# digital_gpio.net
KiCad netlist of a schematic drawn in Altium Designer
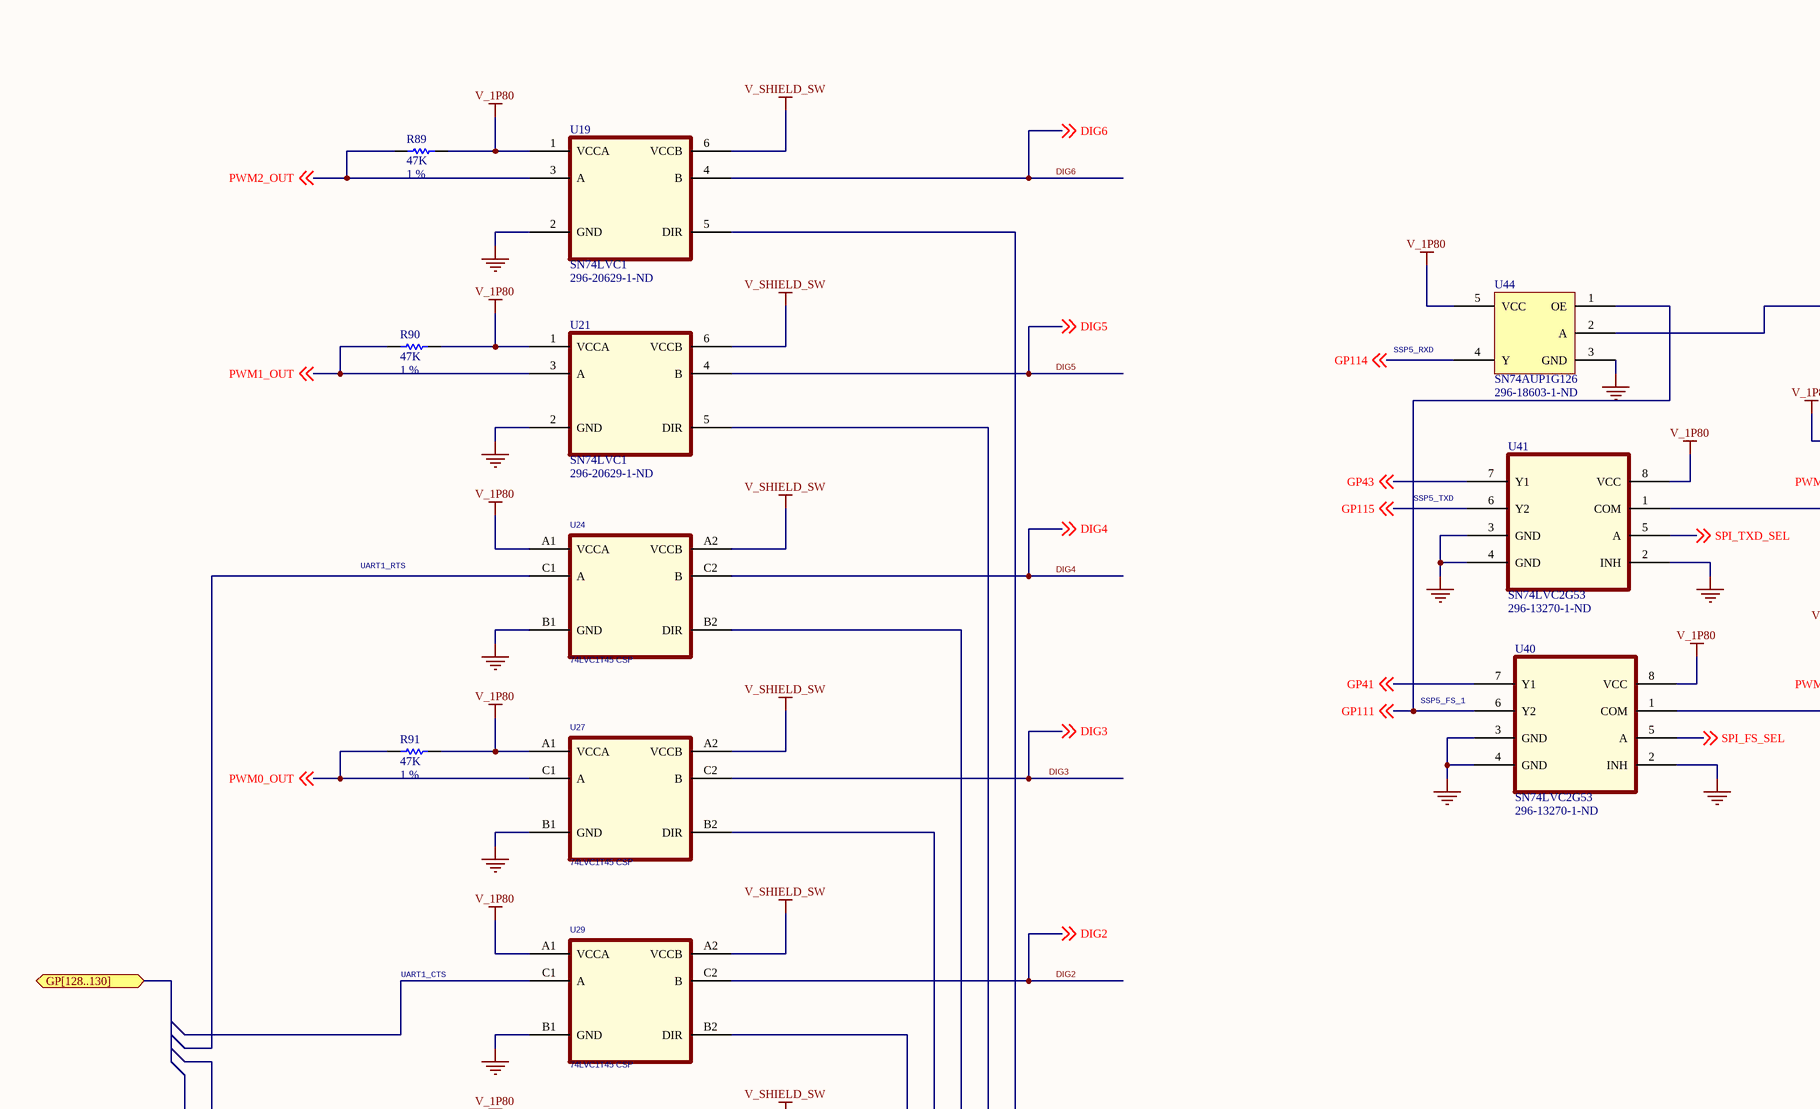
[diagram p0: digital_gpio.SchDoc, top left]
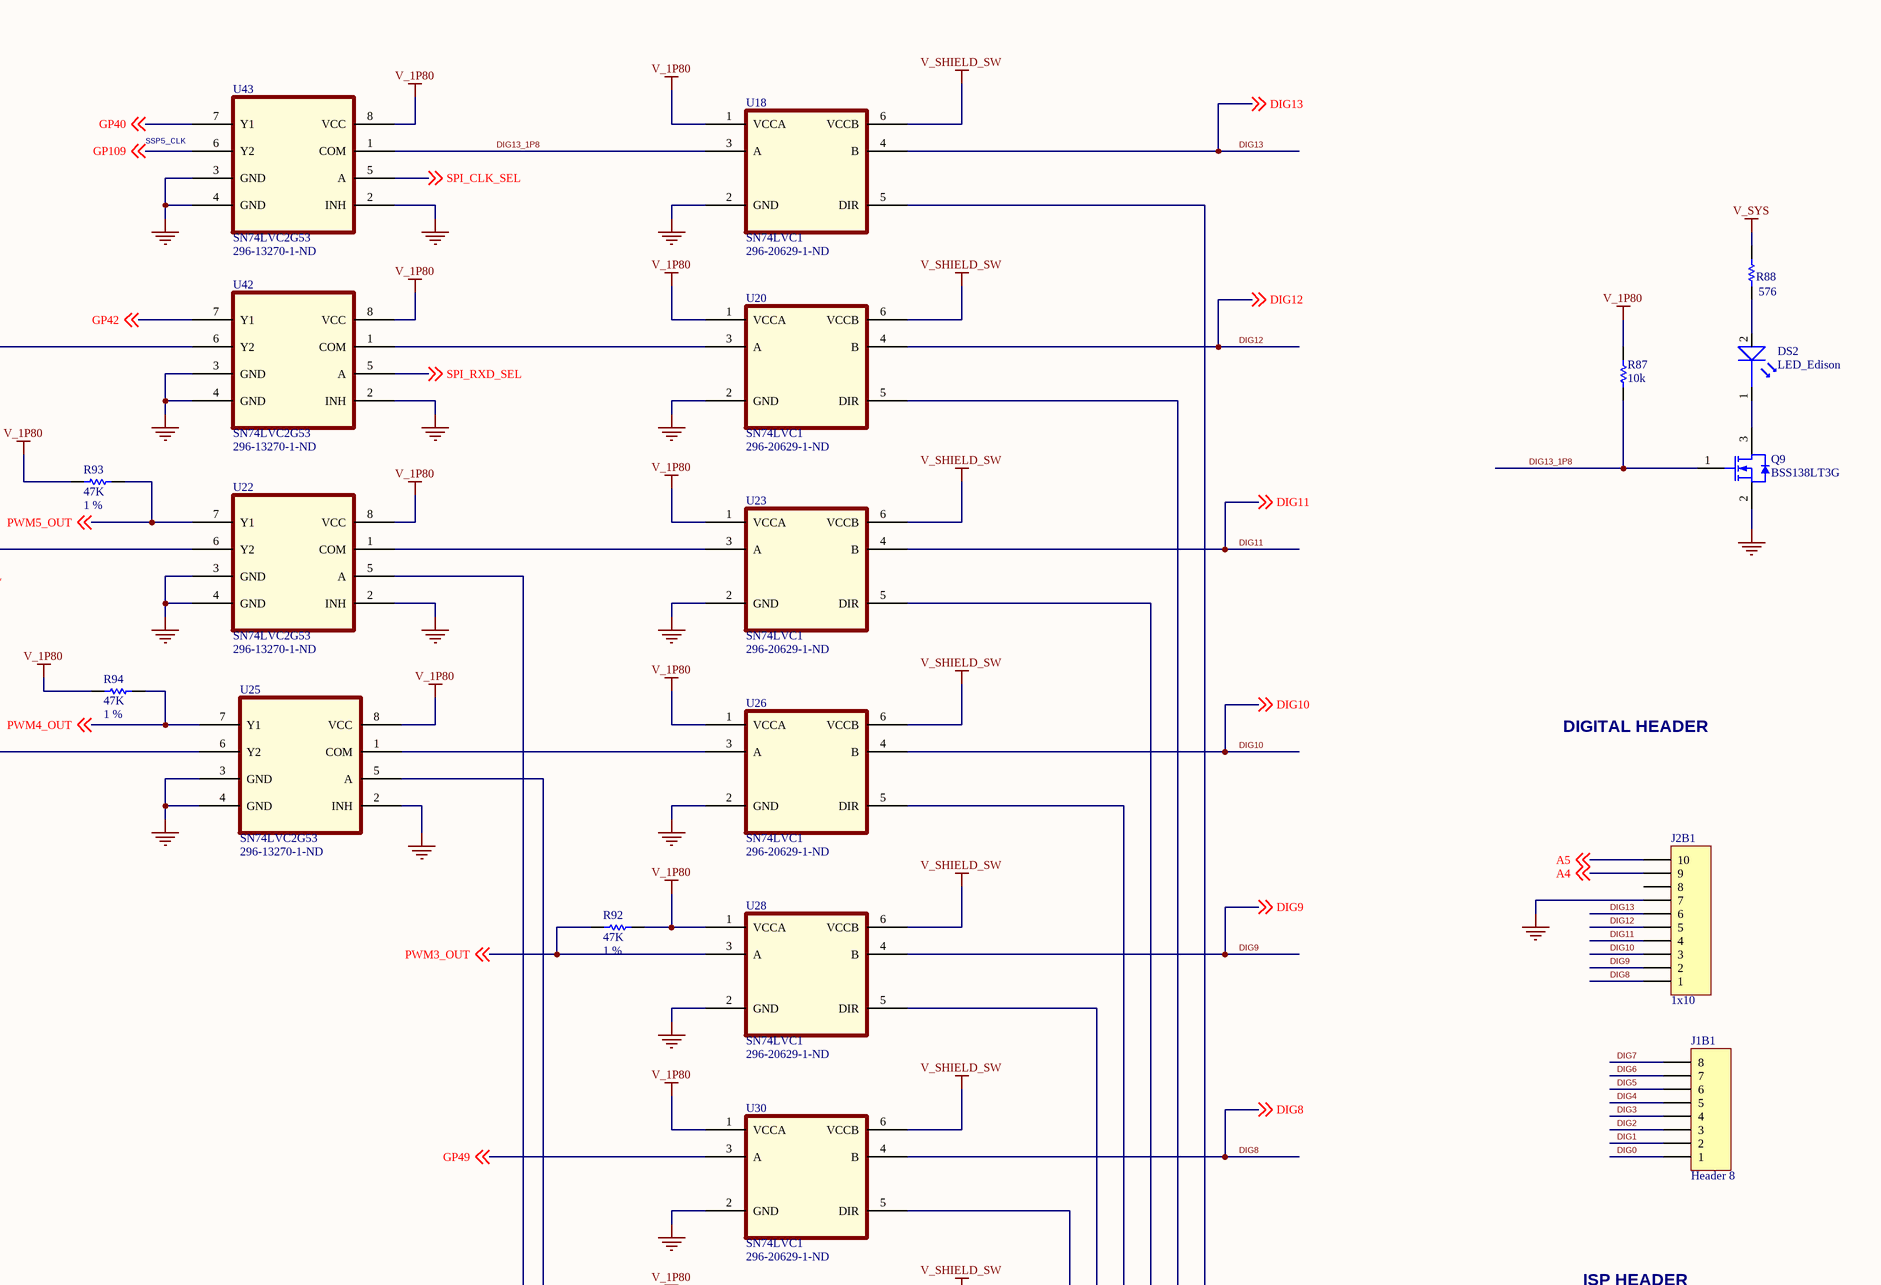
[diagram p1: digital_gpio.SchDoc, top right]
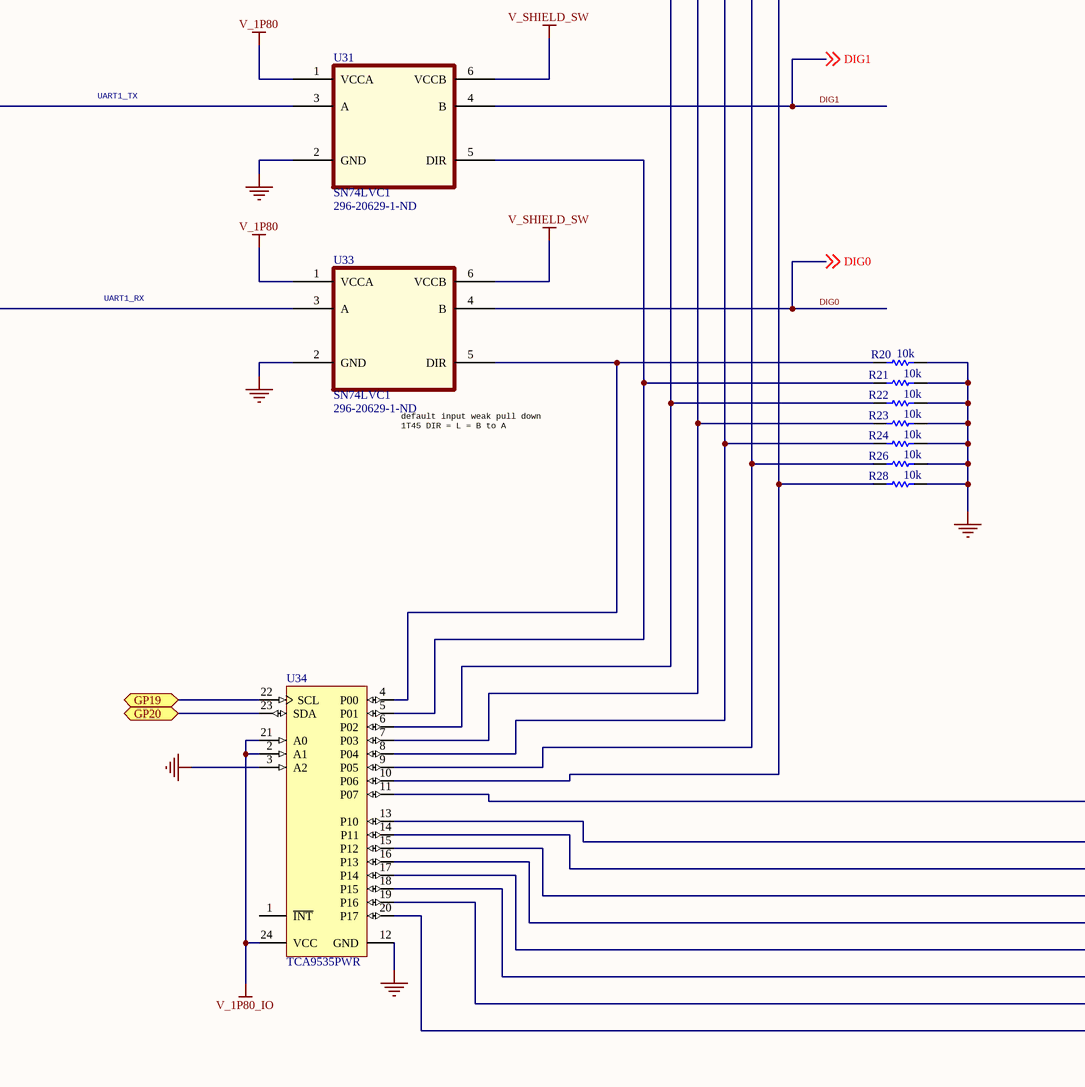
[diagram p2: digital_gpio.SchDoc, bottom left]
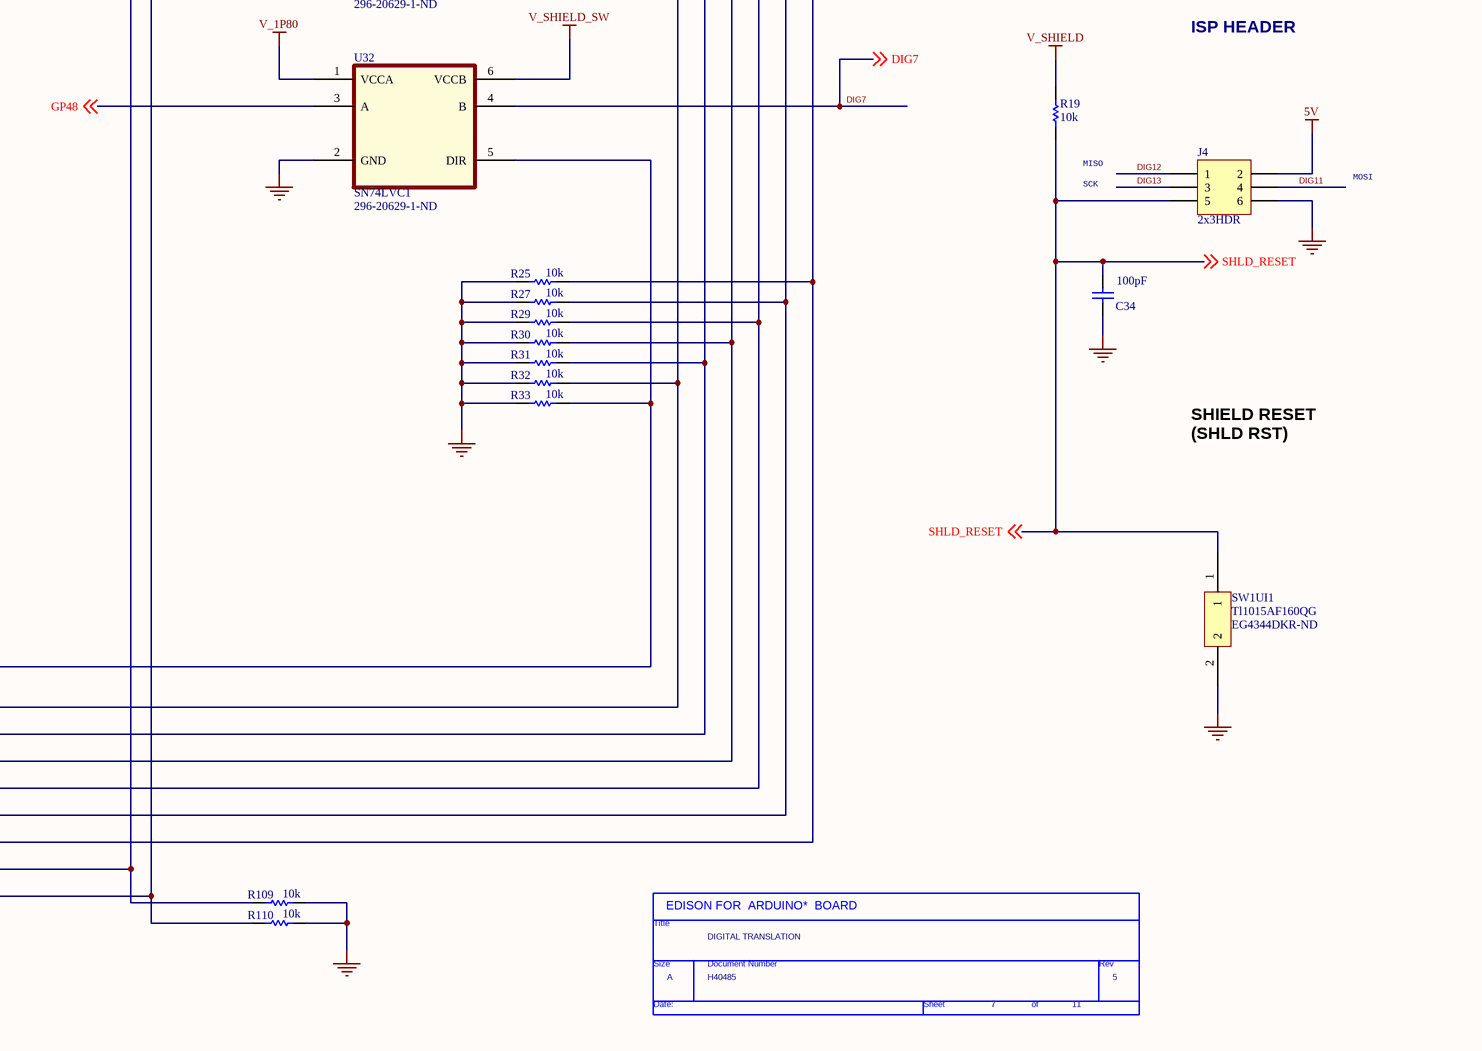
[diagram p3: digital_gpio.SchDoc, bottom right]

(export (version "E")
  (design (tool "Eeschema 10.0.6"))
  (components
    (comp (ref "*")
      (value "TitleBlock0")
      (fields
        (field (name "PAGE COUNT") "11")
        (field (name "PAGE NUMBER") "7")
        (field (name "PAGE SIZE") "A")
        (field (name "TITLE") "DIGITAL TRANSLATION")
        (field (name "REVCODE") "5")
        (field (name "DOC") "H40485")
      )
      (libsource (lib "*") (part "TitleBlock0"))
    )
    (comp (ref "C34")
      (value "100pF")
      (footprint "CAPC0201(0603)33_N")
      (description "CAP 100pF 25V ±5% 0201 (0603 Metric) Thickness 0.33mm SMD")
      (fields (field (name "TOLERANCE") "±5%") (field (name "Comment") "CAP 100pF 25V 0201(0603)"))
      (libsource (lib "Altium Content Vault") (part "CMP-1033-00493-1"))
    )
    (comp (ref "DS2")
      (value "LED_Edison")
      (footprint "LTST-C281KGKT")
      (libsource (lib "elevate_lib") (part "LED_Edison"))
    )
    (comp (ref "J1B1")
      (value "Header 8")
      (footprint "HDR1X8")
      (description "Header, 8-Pin")
      (fields (field (name "PUBLISHER") "Altium Limited"))
      (libsource (lib "Miscellaneous Connectors") (part "Header 8"))
    )
    (comp (ref "J2B1")
      (value "1x10")
      (footprint "HDR1X10")
      (description "Header, 10-Pin")
      (fields (field (name "PUBLISHER") "Altium Limited"))
      (libsource (lib "Miscellaneous Connectors") (part "Header 10"))
    )
    (comp (ref "J4")
      (value "2x3HDR")
      (footprint "HDR2X3")
      (description "Header, 3-Pin, Dual row")
      (fields (field (name "PUBLISHER") "Altium Limited"))
      (libsource (lib "Miscellaneous Connectors") (part "Header 3X2"))
    )
    (comp (ref "Q9")
      (value "BSS138LT3G")
      (footprint "ONSC-SOT-23-3-318-08_V")
      (description "Power MOSFET, 200 mA, 50 V, N-Channel, 3-Pin SOT-23, Pb-Free, Tape and Reel")
      (fields (field (name "MANUFACTURER") "On Semiconductor"))
      (libsource (lib "Altium Content Vault") (part "ONSC-NMOS-G1S2D3-3"))
    )
    (comp (ref "R19")
      (value "10k")
      (footprint "RESC0201(0603)_M")
      (description "165R 0.05W 1% 0201 (0603 Metric)  SMD")
      (fields (field (name "POWER") "0.05 W") (field (name "TOLERANCE") "1 %"))
      (libsource (lib "Altium Content Vault") (part "CMP-1010-00326-1"))
    )
    (comp (ref "R20")
      (value "10k")
      (footprint "RESC0201(0603)_M")
      (description "165R 0.05W 1% 0201 (0603 Metric)  SMD")
      (fields (field (name "POWER") "0.05 W") (field (name "TOLERANCE") "1 %"))
      (libsource (lib "Altium Content Vault") (part "CMP-1010-00326-1"))
    )
    (comp (ref "R21")
      (value "10k")
      (footprint "RESC0201(0603)_M")
      (description "165R 0.05W 1% 0201 (0603 Metric)  SMD")
      (fields (field (name "POWER") "0.05 W") (field (name "TOLERANCE") "1 %"))
      (libsource (lib "Altium Content Vault") (part "CMP-1010-00326-1"))
    )
    (comp (ref "R22")
      (value "10k")
      (footprint "RESC0201(0603)_M")
      (description "165R 0.05W 1% 0201 (0603 Metric)  SMD")
      (fields (field (name "POWER") "0.05 W") (field (name "TOLERANCE") "1 %"))
      (libsource (lib "Altium Content Vault") (part "CMP-1010-00326-1"))
    )
    (comp (ref "R23")
      (value "10k")
      (footprint "RESC0201(0603)_M")
      (description "165R 0.05W 1% 0201 (0603 Metric)  SMD")
      (fields (field (name "POWER") "0.05 W") (field (name "TOLERANCE") "1 %"))
      (libsource (lib "Altium Content Vault") (part "CMP-1010-00326-1"))
    )
    (comp (ref "R24")
      (value "10k")
      (footprint "RESC0201(0603)_M")
      (description "165R 0.05W 1% 0201 (0603 Metric)  SMD")
      (fields (field (name "POWER") "0.05 W") (field (name "TOLERANCE") "1 %"))
      (libsource (lib "Altium Content Vault") (part "CMP-1010-00326-1"))
    )
    (comp (ref "R25")
      (value "10k")
      (footprint "RESC0201(0603)_M")
      (description "165R 0.05W 1% 0201 (0603 Metric)  SMD")
      (fields (field (name "POWER") "0.05 W") (field (name "TOLERANCE") "1 %"))
      (libsource (lib "Altium Content Vault") (part "CMP-1010-00326-1"))
    )
    (comp (ref "R26")
      (value "10k")
      (footprint "RESC0201(0603)_M")
      (description "165R 0.05W 1% 0201 (0603 Metric)  SMD")
      (fields (field (name "POWER") "0.05 W") (field (name "TOLERANCE") "1 %"))
      (libsource (lib "Altium Content Vault") (part "CMP-1010-00326-1"))
    )
    (comp (ref "R27")
      (value "10k")
      (footprint "RESC0201(0603)_M")
      (description "165R 0.05W 1% 0201 (0603 Metric)  SMD")
      (fields (field (name "POWER") "0.05 W") (field (name "TOLERANCE") "1 %"))
      (libsource (lib "Altium Content Vault") (part "CMP-1010-00326-1"))
    )
    (comp (ref "R28")
      (value "10k")
      (footprint "RESC0201(0603)_M")
      (description "165R 0.05W 1% 0201 (0603 Metric)  SMD")
      (fields (field (name "POWER") "0.05 W") (field (name "TOLERANCE") "1 %"))
      (libsource (lib "Altium Content Vault") (part "CMP-1010-00326-1"))
    )
    (comp (ref "R29")
      (value "10k")
      (footprint "RESC0201(0603)_M")
      (description "165R 0.05W 1% 0201 (0603 Metric)  SMD")
      (fields (field (name "POWER") "0.05 W") (field (name "TOLERANCE") "1 %"))
      (libsource (lib "Altium Content Vault") (part "CMP-1010-00326-1"))
    )
    (comp (ref "R30")
      (value "10k")
      (footprint "RESC0201(0603)_M")
      (description "165R 0.05W 1% 0201 (0603 Metric)  SMD")
      (fields (field (name "POWER") "0.05 W") (field (name "TOLERANCE") "1 %"))
      (libsource (lib "Altium Content Vault") (part "CMP-1010-00326-1"))
    )
    (comp (ref "R31")
      (value "10k")
      (footprint "RESC0201(0603)_M")
      (description "165R 0.05W 1% 0201 (0603 Metric)  SMD")
      (fields (field (name "POWER") "0.05 W") (field (name "TOLERANCE") "1 %"))
      (libsource (lib "Altium Content Vault") (part "CMP-1010-00326-1"))
    )
    (comp (ref "R32")
      (value "10k")
      (footprint "RESC0201(0603)_M")
      (description "165R 0.05W 1% 0201 (0603 Metric)  SMD")
      (fields (field (name "POWER") "0.05 W") (field (name "TOLERANCE") "1 %"))
      (libsource (lib "Altium Content Vault") (part "CMP-1010-00326-1"))
    )
    (comp (ref "R33")
      (value "10k")
      (footprint "RESC0201(0603)_M")
      (description "165R 0.05W 1% 0201 (0603 Metric)  SMD")
      (fields (field (name "POWER") "0.05 W") (field (name "TOLERANCE") "1 %"))
      (libsource (lib "Altium Content Vault") (part "CMP-1010-00326-1"))
    )
    (comp (ref "R87")
      (value "10k")
      (footprint "RESC0201(0603)_M")
      (description "165R 0.05W 1% 0201 (0603 Metric)  SMD")
      (fields (field (name "POWER") "0.05 W") (field (name "TOLERANCE") "1 %"))
      (libsource (lib "Altium Content Vault") (part "CMP-1010-00326-1"))
    )
    (comp (ref "R88")
      (value "576")
      (footprint "RESC0402(1005)_L")
      (description "576R 0.063W 1% 0402 (1005 Metric)  SMD")
      (fields (field (name "TOLERANCE") "1 %") (field (name "POWER") "0.063 W"))
      (libsource (lib "Altium Content Vault") (part "CMP-1011-00483-1"))
    )
    (comp (ref "R89")
      (value "47K")
      (footprint "RESC0201(0603)_N")
      (description "47K 0.05W 1% 0201 (0603 Metric)  SMD")
      (fields
        (field (name "TOLERANCE") "1 %")
        (field (name "POWER") "0.05 W")
        (field (name "Comment") "47K 1% 0201(0603)")
      )
      (libsource (lib "Altium Content Vault") (part "CMP-1010-00605-1"))
    )
    (comp (ref "R90")
      (value "47K")
      (footprint "RESC0201(0603)_N")
      (description "47K 0.05W 1% 0201 (0603 Metric)  SMD")
      (fields
        (field (name "TOLERANCE") "1 %")
        (field (name "POWER") "0.05 W")
        (field (name "Comment") "47K 1% 0201(0603)")
      )
      (libsource (lib "Altium Content Vault") (part "CMP-1010-00605-1"))
    )
    (comp (ref "R91")
      (value "47K")
      (footprint "RESC0201(0603)_N")
      (description "47K 0.05W 1% 0201 (0603 Metric)  SMD")
      (fields
        (field (name "TOLERANCE") "1 %")
        (field (name "POWER") "0.05 W")
        (field (name "Comment") "47K 1% 0201(0603)")
      )
      (libsource (lib "Altium Content Vault") (part "CMP-1010-00605-1"))
    )
    (comp (ref "R92")
      (value "47K")
      (footprint "RESC0201(0603)_N")
      (description "47K 0.05W 1% 0201 (0603 Metric)  SMD")
      (fields
        (field (name "TOLERANCE") "1 %")
        (field (name "POWER") "0.05 W")
        (field (name "Comment") "47K 1% 0201(0603)")
      )
      (libsource (lib "Altium Content Vault") (part "CMP-1010-00605-1"))
    )
    (comp (ref "R93")
      (value "47K")
      (footprint "RESC0201(0603)_N")
      (description "47K 0.05W 1% 0201 (0603 Metric)  SMD")
      (fields
        (field (name "TOLERANCE") "1 %")
        (field (name "POWER") "0.05 W")
        (field (name "Comment") "47K 1% 0201(0603)")
      )
      (libsource (lib "Altium Content Vault") (part "CMP-1010-00605-1"))
    )
    (comp (ref "R94")
      (value "47K")
      (footprint "RESC0201(0603)_N")
      (description "47K 0.05W 1% 0201 (0603 Metric)  SMD")
      (fields
        (field (name "TOLERANCE") "1 %")
        (field (name "POWER") "0.05 W")
        (field (name "Comment") "47K 1% 0201(0603)")
      )
      (libsource (lib "Altium Content Vault") (part "CMP-1010-00605-1"))
    )
    (comp (ref "R109")
      (value "10k")
      (footprint "RESC0201(0603)_M")
      (description "165R 0.05W 1% 0201 (0603 Metric)  SMD")
      (fields (field (name "POWER") "0.05 W") (field (name "TOLERANCE") "1 %"))
      (libsource (lib "Altium Content Vault") (part "CMP-1010-00326-1"))
    )
    (comp (ref "R110")
      (value "10k")
      (footprint "RESC0201(0603)_M")
      (description "165R 0.05W 1% 0201 (0603 Metric)  SMD")
      (fields (field (name "POWER") "0.05 W") (field (name "TOLERANCE") "1 %"))
      (libsource (lib "Altium Content Vault") (part "CMP-1010-00326-1"))
    )
    (comp (ref "SW1UI1")
      (value "Tl1015AF160QG")
      (footprint "TL1015AF160QG")
      (fields (field (name "SUPPLIER PART NUMBER 1") "EG4344DKR-ND"))
      (libsource (lib "elevate_lib") (part "Tl1015AF160QG"))
    )
    (comp (ref "U18")
      (value "SN74LVC1")
      (footprint "R-PDSO-N6")
      (fields (field (name "SUPPLIER PART NUMBER 1") "296-20629-1-ND"))
      (libsource (lib "elevate_lib") (part "SN74LVC1"))
    )
    (comp (ref "U19")
      (value "SN74LVC1")
      (footprint "R-PDSO-N6")
      (fields (field (name "SUPPLIER PART NUMBER 1") "296-20629-1-ND"))
      (libsource (lib "elevate_lib") (part "SN74LVC1"))
    )
    (comp (ref "U20")
      (value "SN74LVC1")
      (footprint "R-PDSO-N6")
      (fields (field (name "SUPPLIER PART NUMBER 1") "296-20629-1-ND"))
      (libsource (lib "elevate_lib") (part "SN74LVC1"))
    )
    (comp (ref "U21")
      (value "SN74LVC1")
      (footprint "R-PDSO-N6")
      (fields (field (name "SUPPLIER PART NUMBER 1") "296-20629-1-ND"))
      (libsource (lib "elevate_lib") (part "SN74LVC1"))
    )
    (comp (ref "U22")
      (value "SN74LVC2G53")
      (footprint "S-PSDO-8")
      (fields (field (name "SUPPLIER PART NUMBER 1") "296-13270-1-ND"))
      (libsource (lib "elevate_lib") (part "SN74LVC2G53"))
    )
    (comp (ref "U23")
      (value "SN74LVC1")
      (footprint "R-PDSO-N6")
      (fields (field (name "SUPPLIER PART NUMBER 1") "296-20629-1-ND"))
      (libsource (lib "elevate_lib") (part "SN74LVC1"))
    )
    (comp (ref "U24")
      (value "74LVC1T45 CSP")
      (footprint "bga6_5mm_37x57")
      (description "IC,LOG,TRANSCEIVE,CSP,SN74LVC1T45,NI3S,")
      (fields (field (name "PART_NUMBER") "G42189-001") (field (name "MFG") "TI"))
      (libsource (lib "*") (part "IC,74LVC1T45,LOG,BGA6,TRNSSVR"))
    )
    (comp (ref "U25")
      (value "SN74LVC2G53")
      (footprint "S-PSDO-8")
      (fields (field (name "SUPPLIER PART NUMBER 1") "296-13270-1-ND"))
      (libsource (lib "elevate_lib") (part "SN74LVC2G53"))
    )
    (comp (ref "U26")
      (value "SN74LVC1")
      (footprint "R-PDSO-N6")
      (fields (field (name "SUPPLIER PART NUMBER 1") "296-20629-1-ND"))
      (libsource (lib "elevate_lib") (part "SN74LVC1"))
    )
    (comp (ref "U27")
      (value "74LVC1T45 CSP")
      (footprint "bga6_5mm_37x57")
      (description "IC,LOG,TRANSCEIVE,CSP,SN74LVC1T45,NI3S,")
      (fields (field (name "PART_NUMBER") "G42189-001") (field (name "MFG") "TI"))
      (libsource (lib "*") (part "IC,74LVC1T45,LOG,BGA6,TRNSSVR"))
    )
    (comp (ref "U28")
      (value "SN74LVC1")
      (footprint "R-PDSO-N6")
      (fields (field (name "SUPPLIER PART NUMBER 1") "296-20629-1-ND"))
      (libsource (lib "elevate_lib") (part "SN74LVC1"))
    )
    (comp (ref "U29")
      (value "74LVC1T45 CSP")
      (footprint "bga6_5mm_37x57")
      (description "IC,LOG,TRANSCEIVE,CSP,SN74LVC1T45,NI3S,")
      (fields (field (name "PART_NUMBER") "G42189-001") (field (name "MFG") "TI"))
      (libsource (lib "*") (part "IC,74LVC1T45,LOG,BGA6,TRNSSVR"))
    )
    (comp (ref "U30")
      (value "SN74LVC1")
      (footprint "R-PDSO-N6")
      (fields (field (name "SUPPLIER PART NUMBER 1") "296-20629-1-ND"))
      (libsource (lib "elevate_lib") (part "SN74LVC1"))
    )
    (comp (ref "U31")
      (value "SN74LVC1")
      (footprint "R-PDSO-N6")
      (fields (field (name "SUPPLIER PART NUMBER 1") "296-20629-1-ND"))
      (libsource (lib "elevate_lib") (part "SN74LVC1"))
    )
    (comp (ref "U32")
      (value "SN74LVC1")
      (footprint "R-PDSO-N6")
      (fields (field (name "SUPPLIER PART NUMBER 1") "296-20629-1-ND"))
      (libsource (lib "elevate_lib") (part "SN74LVC1"))
    )
    (comp (ref "U33")
      (value "SN74LVC1")
      (footprint "R-PDSO-N6")
      (fields (field (name "SUPPLIER PART NUMBER 1") "296-20629-1-ND"))
      (libsource (lib "elevate_lib") (part "SN74LVC1"))
    )
    (comp (ref "U34")
      (value "TCA9535PWR")
      (footprint "PW24_N")
      (fields (field (name "MANUFACTURER") "Texas Instruments"))
      (libsource (lib "Altium Content Vault") (part "TI-TCA9535-TSSOP_PW-24"))
    )
    (comp (ref "U40")
      (value "SN74LVC2G53")
      (footprint "S-PSDO-8")
      (fields (field (name "SUPPLIER PART NUMBER 1") "296-13270-1-ND"))
      (libsource (lib "elevate_lib") (part "SN74LVC2G53"))
    )
    (comp (ref "U41")
      (value "SN74LVC2G53")
      (footprint "S-PSDO-8")
      (fields (field (name "SUPPLIER PART NUMBER 1") "296-13270-1-ND"))
      (libsource (lib "elevate_lib") (part "SN74LVC2G53"))
    )
    (comp (ref "U42")
      (value "SN74LVC2G53")
      (footprint "S-PSDO-8")
      (fields (field (name "SUPPLIER PART NUMBER 1") "296-13270-1-ND"))
      (libsource (lib "elevate_lib") (part "SN74LVC2G53"))
    )
    (comp (ref "U43")
      (value "SN74LVC2G53")
      (footprint "S-PSDO-8")
      (fields (field (name "SUPPLIER PART NUMBER 1") "296-13270-1-ND"))
      (libsource (lib "elevate_lib") (part "SN74LVC2G53"))
    )
    (comp (ref "U44")
      (value "SN74AUP1G126")
      (footprint "R-PDS-N5")
      (fields (field (name "SUPPLIER PART NUMBER 1") "296-18603-1-ND"))
      (libsource (lib "elevate_lib") (part "SN74AUP1G126"))
    )
  )
  (nets
    (net (code "4") (name "/DIG13_1P8") (class "Default")
      (node (ref "Q9") (pin "1") (pinfunction "G_1") (pintype "passive"))
      (node (ref "R87") (pin "2") (pinfunction "2_2") (pintype "passive"))
      (node (ref "U18") (pin "3") (pinfunction "A_3") (pintype "passive"))
      (node (ref "U43") (pin "1") (pinfunction "COM_1") (pintype "passive"))
    )
    (net (code "5") (name "/GP19") (class "Default")
      (node (ref "U34") (pin "22") (pinfunction "SCL_22") (pintype "input"))
    )
    (net (code "6") (name "/GP20") (class "Default")
      (node (ref "U34") (pin "23") (pinfunction "SDA_23") (pintype "bidirectional"))
    )
    (net (code "8") (name "5V") (class "Default")
      (node (ref "J4") (pin "2") (pinfunction "2_2") (pintype "passive"))
    )
    (net (code "9") (name "A4") (class "Default")
      (node (ref "J2B1") (pin "9") (pinfunction "9_9") (pintype "passive"))
    )
    (net (code "10") (name "A5") (class "Default")
      (node (ref "J2B1") (pin "10") (pinfunction "10_10") (pintype "passive"))
    )
    (net (code "11") (name "DIG0") (class "Default")
      (node (ref "J1B1") (pin "1") (pinfunction "1_1") (pintype "passive"))
      (node (ref "U33") (pin "4") (pinfunction "B_4") (pintype "passive"))
    )
    (net (code "12") (name "DIG1") (class "Default")
      (node (ref "J1B1") (pin "2") (pinfunction "2_2") (pintype "passive"))
      (node (ref "U31") (pin "4") (pinfunction "B_4") (pintype "passive"))
    )
    (net (code "13") (name "DIG2") (class "Default")
      (node (ref "J1B1") (pin "3") (pinfunction "3_3") (pintype "passive"))
      (node (ref "U29") (pin "C2") (pinfunction "B_C2") (pintype "passive"))
    )
    (net (code "14") (name "DIG3") (class "Default")
      (node (ref "J1B1") (pin "4") (pinfunction "4_4") (pintype "passive"))
      (node (ref "U27") (pin "C2") (pinfunction "B_C2") (pintype "passive"))
    )
    (net (code "15") (name "DIG4") (class "Default")
      (node (ref "J1B1") (pin "5") (pinfunction "5_5") (pintype "passive"))
      (node (ref "U24") (pin "C2") (pinfunction "B_C2") (pintype "passive"))
    )
    (net (code "16") (name "DIG5") (class "Default")
      (node (ref "J1B1") (pin "6") (pinfunction "6_6") (pintype "passive"))
      (node (ref "U21") (pin "4") (pinfunction "B_4") (pintype "passive"))
    )
    (net (code "17") (name "DIG6") (class "Default")
      (node (ref "J1B1") (pin "7") (pinfunction "7_7") (pintype "passive"))
      (node (ref "U19") (pin "4") (pinfunction "B_4") (pintype "passive"))
    )
    (net (code "18") (name "DIG7") (class "Default")
      (node (ref "J1B1") (pin "8") (pinfunction "8_8") (pintype "passive"))
      (node (ref "U32") (pin "4") (pinfunction "B_4") (pintype "passive"))
    )
    (net (code "19") (name "DIG8") (class "Default")
      (node (ref "J2B1") (pin "1") (pinfunction "1_1") (pintype "passive"))
      (node (ref "U30") (pin "4") (pinfunction "B_4") (pintype "passive"))
    )
    (net (code "20") (name "DIG9") (class "Default")
      (node (ref "J2B1") (pin "2") (pinfunction "2_2") (pintype "passive"))
      (node (ref "U28") (pin "4") (pinfunction "B_4") (pintype "passive"))
    )
    (net (code "21") (name "DIG10") (class "Default")
      (node (ref "J2B1") (pin "3") (pinfunction "3_3") (pintype "passive"))
      (node (ref "U26") (pin "4") (pinfunction "B_4") (pintype "passive"))
    )
    (net (code "22") (name "DIG11") (class "Default")
      (node (ref "J2B1") (pin "4") (pinfunction "4_4") (pintype "passive"))
      (node (ref "J4") (pin "4") (pinfunction "4_4") (pintype "passive"))
      (node (ref "U23") (pin "4") (pinfunction "B_4") (pintype "passive"))
    )
    (net (code "23") (name "DIG12") (class "Default")
      (node (ref "J2B1") (pin "5") (pinfunction "5_5") (pintype "passive"))
      (node (ref "J4") (pin "1") (pinfunction "1_1") (pintype "passive"))
      (node (ref "U20") (pin "4") (pinfunction "B_4") (pintype "passive"))
    )
    (net (code "24") (name "DIG13") (class "Default")
      (node (ref "J2B1") (pin "6") (pinfunction "6_6") (pintype "passive"))
      (node (ref "J4") (pin "3") (pinfunction "3_3") (pintype "passive"))
      (node (ref "U18") (pin "4") (pinfunction "B_4") (pintype "passive"))
    )
    (net (code "25") (name "GND") (class "Default")
      (node (ref "C34") (pin "2") (pinfunction "2_2") (pintype "passive"))
      (node (ref "J2B1") (pin "7") (pinfunction "7_7") (pintype "passive"))
      (node (ref "J4") (pin "6") (pinfunction "6_6") (pintype "passive"))
      (node (ref "Q9") (pin "2") (pinfunction "S_2") (pintype "passive"))
      (node (ref "R109") (pin "1") (pinfunction "1_1") (pintype "passive"))
      (node (ref "R110") (pin "1") (pinfunction "1_1") (pintype "passive"))
      (node (ref "R20") (pin "1") (pinfunction "1_1") (pintype "passive"))
      (node (ref "R21") (pin "1") (pinfunction "1_1") (pintype "passive"))
      (node (ref "R22") (pin "1") (pinfunction "1_1") (pintype "passive"))
      (node (ref "R23") (pin "1") (pinfunction "1_1") (pintype "passive"))
      (node (ref "R24") (pin "1") (pinfunction "1_1") (pintype "passive"))
      (node (ref "R25") (pin "2") (pinfunction "2_2") (pintype "passive"))
      (node (ref "R26") (pin "1") (pinfunction "1_1") (pintype "passive"))
      (node (ref "R27") (pin "2") (pinfunction "2_2") (pintype "passive"))
      (node (ref "R28") (pin "1") (pinfunction "1_1") (pintype "passive"))
      (node (ref "R29") (pin "2") (pinfunction "2_2") (pintype "passive"))
      (node (ref "R30") (pin "2") (pinfunction "2_2") (pintype "passive"))
      (node (ref "R31") (pin "2") (pinfunction "2_2") (pintype "passive"))
      (node (ref "R32") (pin "2") (pinfunction "2_2") (pintype "passive"))
      (node (ref "R33") (pin "2") (pinfunction "2_2") (pintype "passive"))
      (node (ref "SW1UI1") (pin "2") (pinfunction "2_2") (pintype "passive"))
      (node (ref "U18") (pin "2") (pinfunction "GND_2") (pintype "passive"))
      (node (ref "U19") (pin "2") (pinfunction "GND_2") (pintype "passive"))
      (node (ref "U20") (pin "2") (pinfunction "GND_2") (pintype "passive"))
      (node (ref "U21") (pin "2") (pinfunction "GND_2") (pintype "passive"))
      (node (ref "U22") (pin "2") (pinfunction "INH_2") (pintype "passive"))
      (node (ref "U22") (pin "3") (pinfunction "GND_3") (pintype "passive"))
      (node (ref "U22") (pin "4") (pinfunction "GND_4") (pintype "passive"))
      (node (ref "U23") (pin "2") (pinfunction "GND_2") (pintype "passive"))
      (node (ref "U24") (pin "B1") (pinfunction "GND_B1") (pintype "passive"))
      (node (ref "U25") (pin "2") (pinfunction "INH_2") (pintype "passive"))
      (node (ref "U25") (pin "3") (pinfunction "GND_3") (pintype "passive"))
      (node (ref "U25") (pin "4") (pinfunction "GND_4") (pintype "passive"))
      (node (ref "U26") (pin "2") (pinfunction "GND_2") (pintype "passive"))
      (node (ref "U27") (pin "B1") (pinfunction "GND_B1") (pintype "passive"))
      (node (ref "U28") (pin "2") (pinfunction "GND_2") (pintype "passive"))
      (node (ref "U29") (pin "B1") (pinfunction "GND_B1") (pintype "passive"))
      (node (ref "U30") (pin "2") (pinfunction "GND_2") (pintype "passive"))
      (node (ref "U31") (pin "2") (pinfunction "GND_2") (pintype "passive"))
      (node (ref "U32") (pin "2") (pinfunction "GND_2") (pintype "passive"))
      (node (ref "U33") (pin "2") (pinfunction "GND_2") (pintype "passive"))
      (node (ref "U34") (pin "12") (pinfunction "GND_12") (pintype "power_in"))
      (node (ref "U34") (pin "3") (pinfunction "A2_3") (pintype "input"))
      (node (ref "U40") (pin "2") (pinfunction "INH_2") (pintype "passive"))
      (node (ref "U40") (pin "3") (pinfunction "GND_3") (pintype "passive"))
      (node (ref "U40") (pin "4") (pinfunction "GND_4") (pintype "passive"))
      (node (ref "U41") (pin "2") (pinfunction "INH_2") (pintype "passive"))
      (node (ref "U41") (pin "3") (pinfunction "GND_3") (pintype "passive"))
      (node (ref "U41") (pin "4") (pinfunction "GND_4") (pintype "passive"))
      (node (ref "U42") (pin "2") (pinfunction "INH_2") (pintype "passive"))
      (node (ref "U42") (pin "3") (pinfunction "GND_3") (pintype "passive"))
      (node (ref "U42") (pin "4") (pinfunction "GND_4") (pintype "passive"))
      (node (ref "U43") (pin "2") (pinfunction "INH_2") (pintype "passive"))
      (node (ref "U43") (pin "3") (pinfunction "GND_3") (pintype "passive"))
      (node (ref "U43") (pin "4") (pinfunction "GND_4") (pintype "passive"))
      (node (ref "U44") (pin "3") (pinfunction "GND_3") (pintype "passive"))
    )
    (net (code "26") (name "GP40") (class "Default")
      (node (ref "U43") (pin "7") (pinfunction "Y1_7") (pintype "passive"))
    )
    (net (code "27") (name "GP41") (class "Default")
      (node (ref "U40") (pin "7") (pinfunction "Y1_7") (pintype "passive"))
    )
    (net (code "28") (name "GP42") (class "Default")
      (node (ref "U42") (pin "7") (pinfunction "Y1_7") (pintype "passive"))
    )
    (net (code "29") (name "GP43") (class "Default")
      (node (ref "U41") (pin "7") (pinfunction "Y1_7") (pintype "passive"))
    )
    (net (code "30") (name "GP48") (class "Default")
      (node (ref "U32") (pin "3") (pinfunction "A_3") (pintype "passive"))
    )
    (net (code "31") (name "GP49") (class "Default")
      (node (ref "U30") (pin "3") (pinfunction "A_3") (pintype "passive"))
    )
    (net (code "32") (name "GP109") (class "Default")
      (node (ref "U43") (pin "6") (pinfunction "Y2_6") (pintype "passive"))
    )
    (net (code "33") (name "GP111") (class "Default")
      (node (ref "U40") (pin "6") (pinfunction "Y2_6") (pintype "passive"))
      (node (ref "U44") (pin "1") (pinfunction "OE_1") (pintype "passive"))
    )
    (net (code "34") (name "GP114") (class "Default")
      (node (ref "U44") (pin "4") (pinfunction "Y_4") (pintype "passive"))
    )
    (net (code "35") (name "GP115") (class "Default")
      (node (ref "U41") (pin "6") (pinfunction "Y2_6") (pintype "passive"))
    )
    (net (code "36") (name "Net-(DS2-LED1)") (class "Default")
      (node (ref "DS2") (pin "1") (pinfunction "LED1_1") (pintype "passive"))
      (node (ref "Q9") (pin "3") (pinfunction "D_3") (pintype "passive"))
    )
    (net (code "37") (name "Net-(DS2-LED2)") (class "Default")
      (node (ref "DS2") (pin "2") (pinfunction "LED2_2") (pintype "passive"))
      (node (ref "R88") (pin "1") (pinfunction "1_1") (pintype "passive"))
    )
    (net (code "38") (name "Net-(U18-DIR)") (class "Default")
      (node (ref "R25") (pin "1") (pinfunction "1_1") (pintype "passive"))
      (node (ref "U18") (pin "5") (pinfunction "DIR_5") (pintype "passive"))
      (node (ref "U34") (pin "18") (pinfunction "P15_18") (pintype "bidirectional"))
    )
    (net (code "39") (name "Net-(U19-DIR)") (class "Default")
      (node (ref "R28") (pin "2") (pinfunction "2_2") (pintype "passive"))
      (node (ref "U19") (pin "5") (pinfunction "DIR_5") (pintype "passive"))
      (node (ref "U34") (pin "10") (pinfunction "P06_10") (pintype "bidirectional"))
    )
    (net (code "40") (name "Net-(U20-A)") (class "Default")
      (node (ref "U20") (pin "3") (pinfunction "A_3") (pintype "passive"))
      (node (ref "U42") (pin "1") (pinfunction "COM_1") (pintype "passive"))
    )
    (net (code "41") (name "Net-(U20-DIR)") (class "Default")
      (node (ref "R27") (pin "1") (pinfunction "1_1") (pintype "passive"))
      (node (ref "U20") (pin "5") (pinfunction "DIR_5") (pintype "passive"))
      (node (ref "U34") (pin "17") (pinfunction "P14_17") (pintype "bidirectional"))
    )
    (net (code "42") (name "Net-(U21-DIR)") (class "Default")
      (node (ref "R26") (pin "2") (pinfunction "2_2") (pintype "passive"))
      (node (ref "U21") (pin "5") (pinfunction "DIR_5") (pintype "passive"))
      (node (ref "U34") (pin "9") (pinfunction "P05_9") (pintype "bidirectional"))
    )
    (net (code "43") (name "Net-(U22-A)") (class "Default")
      (node (ref "R109") (pin "2") (pinfunction "2_2") (pintype "passive"))
      (node (ref "U22") (pin "5") (pinfunction "A_5") (pintype "passive"))
      (node (ref "U34") (pin "19") (pinfunction "P16_19") (pintype "bidirectional"))
    )
    (net (code "44") (name "Net-(U22-COM)") (class "Default")
      (node (ref "U22") (pin "1") (pinfunction "COM_1") (pintype "passive"))
      (node (ref "U23") (pin "3") (pinfunction "A_3") (pintype "passive"))
    )
    (net (code "45") (name "Net-(U22-Y2)") (class "Default")
      (node (ref "U22") (pin "6") (pinfunction "Y2_6") (pintype "passive"))
      (node (ref "U41") (pin "1") (pinfunction "COM_1") (pintype "passive"))
    )
    (net (code "46") (name "Net-(U23-DIR)") (class "Default")
      (node (ref "R29") (pin "1") (pinfunction "1_1") (pintype "passive"))
      (node (ref "U23") (pin "5") (pinfunction "DIR_5") (pintype "passive"))
      (node (ref "U34") (pin "16") (pinfunction "P13_16") (pintype "bidirectional"))
    )
    (net (code "47") (name "Net-(U24-DIR)") (class "Default")
      (node (ref "R24") (pin "2") (pinfunction "2_2") (pintype "passive"))
      (node (ref "U24") (pin "B2") (pinfunction "DIR_B2") (pintype "passive"))
      (node (ref "U34") (pin "8") (pinfunction "P04_8") (pintype "bidirectional"))
    )
    (net (code "48") (name "Net-(U25-A)") (class "Default")
      (node (ref "R110") (pin "2") (pinfunction "2_2") (pintype "passive"))
      (node (ref "U25") (pin "5") (pinfunction "A_5") (pintype "passive"))
      (node (ref "U34") (pin "20") (pinfunction "P17_20") (pintype "bidirectional"))
    )
    (net (code "49") (name "Net-(U25-COM)") (class "Default")
      (node (ref "U25") (pin "1") (pinfunction "COM_1") (pintype "passive"))
      (node (ref "U26") (pin "3") (pinfunction "A_3") (pintype "passive"))
    )
    (net (code "50") (name "Net-(U25-Y2)") (class "Default")
      (node (ref "U25") (pin "6") (pinfunction "Y2_6") (pintype "passive"))
      (node (ref "U40") (pin "1") (pinfunction "COM_1") (pintype "passive"))
    )
    (net (code "51") (name "Net-(U26-DIR)") (class "Default")
      (node (ref "R30") (pin "1") (pinfunction "1_1") (pintype "passive"))
      (node (ref "U26") (pin "5") (pinfunction "DIR_5") (pintype "passive"))
      (node (ref "U34") (pin "15") (pinfunction "P12_15") (pintype "bidirectional"))
    )
    (net (code "52") (name "Net-(U27-DIR)") (class "Default")
      (node (ref "R23") (pin "2") (pinfunction "2_2") (pintype "passive"))
      (node (ref "U27") (pin "B2") (pinfunction "DIR_B2") (pintype "passive"))
      (node (ref "U34") (pin "7") (pinfunction "P03_7") (pintype "bidirectional"))
    )
    (net (code "53") (name "Net-(U28-DIR)") (class "Default")
      (node (ref "R31") (pin "1") (pinfunction "1_1") (pintype "passive"))
      (node (ref "U28") (pin "5") (pinfunction "DIR_5") (pintype "passive"))
      (node (ref "U34") (pin "14") (pinfunction "P11_14") (pintype "bidirectional"))
    )
    (net (code "54") (name "Net-(U29-DIR)") (class "Default")
      (node (ref "R22") (pin "2") (pinfunction "2_2") (pintype "passive"))
      (node (ref "U29") (pin "B2") (pinfunction "DIR_B2") (pintype "passive"))
      (node (ref "U34") (pin "6") (pinfunction "P02_6") (pintype "bidirectional"))
    )
    (net (code "55") (name "Net-(U30-DIR)") (class "Default")
      (node (ref "R32") (pin "1") (pinfunction "1_1") (pintype "passive"))
      (node (ref "U30") (pin "5") (pinfunction "DIR_5") (pintype "passive"))
      (node (ref "U34") (pin "13") (pinfunction "P10_13") (pintype "bidirectional"))
    )
    (net (code "56") (name "Net-(U31-DIR)") (class "Default")
      (node (ref "R21") (pin "2") (pinfunction "2_2") (pintype "passive"))
      (node (ref "U31") (pin "5") (pinfunction "DIR_5") (pintype "passive"))
      (node (ref "U34") (pin "5") (pinfunction "P01_5") (pintype "bidirectional"))
    )
    (net (code "57") (name "Net-(U32-DIR)") (class "Default")
      (node (ref "R33") (pin "1") (pinfunction "1_1") (pintype "passive"))
      (node (ref "U32") (pin "5") (pinfunction "DIR_5") (pintype "passive"))
      (node (ref "U34") (pin "11") (pinfunction "P07_11") (pintype "bidirectional"))
    )
    (net (code "58") (name "Net-(U33-DIR)") (class "Default")
      (node (ref "R20") (pin "2") (pinfunction "2_2") (pintype "passive"))
      (node (ref "U33") (pin "5") (pinfunction "DIR_5") (pintype "passive"))
      (node (ref "U34") (pin "4") (pinfunction "P00_4") (pintype "bidirectional"))
    )
    (net (code "59") (name "Net-(U42-Y2)") (class "Default")
      (node (ref "U42") (pin "6") (pinfunction "Y2_6") (pintype "passive"))
      (node (ref "U44") (pin "2") (pinfunction "A_2") (pintype "passive"))
    )
    (net (code "60") (name "PWM0_OUT") (class "Default")
      (node (ref "R91") (pin "2") (pinfunction "2_2") (pintype "passive"))
      (node (ref "U27") (pin "C1") (pinfunction "A_C1") (pintype "passive"))
    )
    (net (code "61") (name "PWM1_OUT") (class "Default")
      (node (ref "R90") (pin "2") (pinfunction "2_2") (pintype "passive"))
      (node (ref "U21") (pin "3") (pinfunction "A_3") (pintype "passive"))
    )
    (net (code "62") (name "PWM2_OUT") (class "Default")
      (node (ref "R89") (pin "2") (pinfunction "2_2") (pintype "passive"))
      (node (ref "U19") (pin "3") (pinfunction "A_3") (pintype "passive"))
    )
    (net (code "63") (name "PWM3_OUT") (class "Default")
      (node (ref "R92") (pin "2") (pinfunction "2_2") (pintype "passive"))
      (node (ref "U28") (pin "3") (pinfunction "A_3") (pintype "passive"))
    )
    (net (code "64") (name "PWM4_OUT") (class "Default")
      (node (ref "R94") (pin "1") (pinfunction "1_1") (pintype "passive"))
      (node (ref "U25") (pin "7") (pinfunction "Y1_7") (pintype "passive"))
    )
    (net (code "65") (name "PWM5_OUT") (class "Default")
      (node (ref "R93") (pin "1") (pinfunction "1_1") (pintype "passive"))
      (node (ref "U22") (pin "7") (pinfunction "Y1_7") (pintype "passive"))
    )
    (net (code "66") (name "SHLD_RESET") (class "Default")
      (node (ref "C34") (pin "1") (pinfunction "1_1") (pintype "passive"))
      (node (ref "J4") (pin "5") (pinfunction "5_5") (pintype "passive"))
      (node (ref "R19") (pin "2") (pinfunction "2_2") (pintype "passive"))
      (node (ref "SW1UI1") (pin "1") (pinfunction "1_1") (pintype "passive"))
    )
    (net (code "67") (name "SPI_CLK_SEL") (class "Default")
      (node (ref "U43") (pin "5") (pinfunction "A_5") (pintype "passive"))
    )
    (net (code "68") (name "SPI_FS_SEL") (class "Default")
      (node (ref "U40") (pin "5") (pinfunction "A_5") (pintype "passive"))
    )
    (net (code "69") (name "SPI_RXD_SEL") (class "Default")
      (node (ref "U42") (pin "5") (pinfunction "A_5") (pintype "passive"))
    )
    (net (code "70") (name "SPI_TXD_SEL") (class "Default")
      (node (ref "U41") (pin "5") (pinfunction "A_5") (pintype "passive"))
    )
    (net (code "71") (name "V_1P80") (class "Default")
      (node (ref "R87") (pin "1") (pinfunction "1_1") (pintype "passive"))
      (node (ref "R89") (pin "1") (pinfunction "1_1") (pintype "passive"))
      (node (ref "R90") (pin "1") (pinfunction "1_1") (pintype "passive"))
      (node (ref "R91") (pin "1") (pinfunction "1_1") (pintype "passive"))
      (node (ref "R92") (pin "1") (pinfunction "1_1") (pintype "passive"))
      (node (ref "R93") (pin "2") (pinfunction "2_2") (pintype "passive"))
      (node (ref "R94") (pin "2") (pinfunction "2_2") (pintype "passive"))
      (node (ref "U18") (pin "1") (pinfunction "VCCA_1") (pintype "passive"))
      (node (ref "U19") (pin "1") (pinfunction "VCCA_1") (pintype "passive"))
      (node (ref "U20") (pin "1") (pinfunction "VCCA_1") (pintype "passive"))
      (node (ref "U21") (pin "1") (pinfunction "VCCA_1") (pintype "passive"))
      (node (ref "U22") (pin "8") (pinfunction "VCC_8") (pintype "passive"))
      (node (ref "U23") (pin "1") (pinfunction "VCCA_1") (pintype "passive"))
      (node (ref "U24") (pin "A1") (pinfunction "VCCA_A1") (pintype "passive"))
      (node (ref "U25") (pin "8") (pinfunction "VCC_8") (pintype "passive"))
      (node (ref "U26") (pin "1") (pinfunction "VCCA_1") (pintype "passive"))
      (node (ref "U27") (pin "A1") (pinfunction "VCCA_A1") (pintype "passive"))
      (node (ref "U28") (pin "1") (pinfunction "VCCA_1") (pintype "passive"))
      (node (ref "U29") (pin "A1") (pinfunction "VCCA_A1") (pintype "passive"))
      (node (ref "U30") (pin "1") (pinfunction "VCCA_1") (pintype "passive"))
      (node (ref "U31") (pin "1") (pinfunction "VCCA_1") (pintype "passive"))
      (node (ref "U32") (pin "1") (pinfunction "VCCA_1") (pintype "passive"))
      (node (ref "U33") (pin "1") (pinfunction "VCCA_1") (pintype "passive"))
      (node (ref "U40") (pin "8") (pinfunction "VCC_8") (pintype "passive"))
      (node (ref "U41") (pin "8") (pinfunction "VCC_8") (pintype "passive"))
      (node (ref "U42") (pin "8") (pinfunction "VCC_8") (pintype "passive"))
      (node (ref "U43") (pin "8") (pinfunction "VCC_8") (pintype "passive"))
      (node (ref "U44") (pin "5") (pinfunction "VCC_5") (pintype "passive"))
    )
    (net (code "72") (name "V_1P80_IO") (class "Default")
      (node (ref "U34") (pin "2") (pinfunction "A1_2") (pintype "input"))
      (node (ref "U34") (pin "21") (pinfunction "A0_21") (pintype "input"))
      (node (ref "U34") (pin "24") (pinfunction "VCC_24") (pintype "power_in"))
    )
    (net (code "73") (name "V_SHIELD") (class "Default")
      (node (ref "R19") (pin "1") (pinfunction "1_1") (pintype "passive"))
    )
    (net (code "74") (name "V_SHIELD_SW") (class "Default")
      (node (ref "U18") (pin "6") (pinfunction "VCCB_6") (pintype "passive"))
      (node (ref "U19") (pin "6") (pinfunction "VCCB_6") (pintype "passive"))
      (node (ref "U20") (pin "6") (pinfunction "VCCB_6") (pintype "passive"))
      (node (ref "U21") (pin "6") (pinfunction "VCCB_6") (pintype "passive"))
      (node (ref "U23") (pin "6") (pinfunction "VCCB_6") (pintype "passive"))
      (node (ref "U24") (pin "A2") (pinfunction "VCCB_A2") (pintype "passive"))
      (node (ref "U26") (pin "6") (pinfunction "VCCB_6") (pintype "passive"))
      (node (ref "U27") (pin "A2") (pinfunction "VCCB_A2") (pintype "passive"))
      (node (ref "U28") (pin "6") (pinfunction "VCCB_6") (pintype "passive"))
      (node (ref "U29") (pin "A2") (pinfunction "VCCB_A2") (pintype "passive"))
      (node (ref "U30") (pin "6") (pinfunction "VCCB_6") (pintype "passive"))
      (node (ref "U31") (pin "6") (pinfunction "VCCB_6") (pintype "passive"))
      (node (ref "U32") (pin "6") (pinfunction "VCCB_6") (pintype "passive"))
      (node (ref "U33") (pin "6") (pinfunction "VCCB_6") (pintype "passive"))
    )
    (net (code "75") (name "V_SYS") (class "Default")
      (node (ref "R88") (pin "2") (pinfunction "2_2") (pintype "passive"))
    )
    (net (code "76") (name "unconnected-(J2B1-Pad8)") (class "Default")
      (node (ref "J2B1") (pin "8") (pinfunction "8_8") (pintype "passive"))
    )
    (net (code "77") (name "unconnected-(U24-A-PadC1)") (class "Default")
      (node (ref "U24") (pin "C1") (pinfunction "A_C1") (pintype "passive"))
    )
    (net (code "78") (name "unconnected-(U29-A-PadC1)") (class "Default")
      (node (ref "U29") (pin "C1") (pinfunction "A_C1") (pintype "passive"))
    )
    (net (code "79") (name "unconnected-(U31-A-Pad3)") (class "Default")
      (node (ref "U31") (pin "3") (pinfunction "A_3") (pintype "passive"))
    )
    (net (code "80") (name "unconnected-(U33-A-Pad3)") (class "Default")
      (node (ref "U33") (pin "3") (pinfunction "A_3") (pintype "passive"))
    )
    (net (code "81") (name "unconnected-(U34-~{INT}-Pad1)") (class "Default")
      (node (ref "U34") (pin "1") (pinfunction "~{INT}_1") (pintype "open_collector"))
    )
  )
)
